# DC075B_DEVICE_PINOUT.net
KiCad netlist of a schematic drawn in Altium Designer
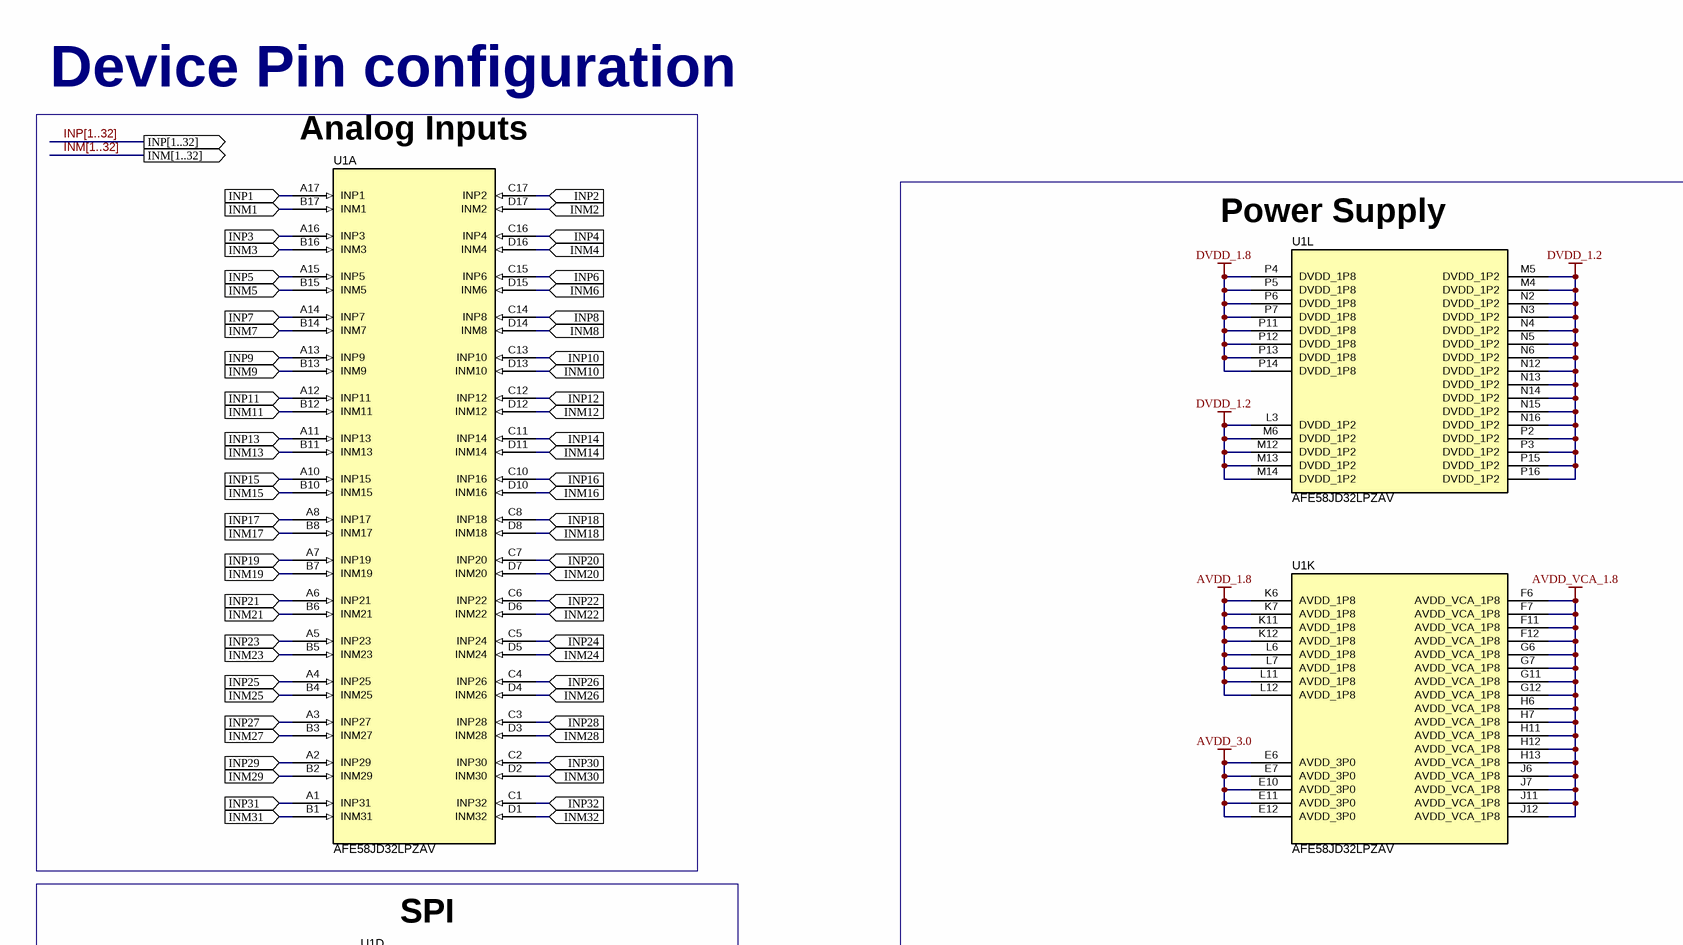
[diagram p0: DC075B_DEVICE_PINOUT.SchDoc, top left]
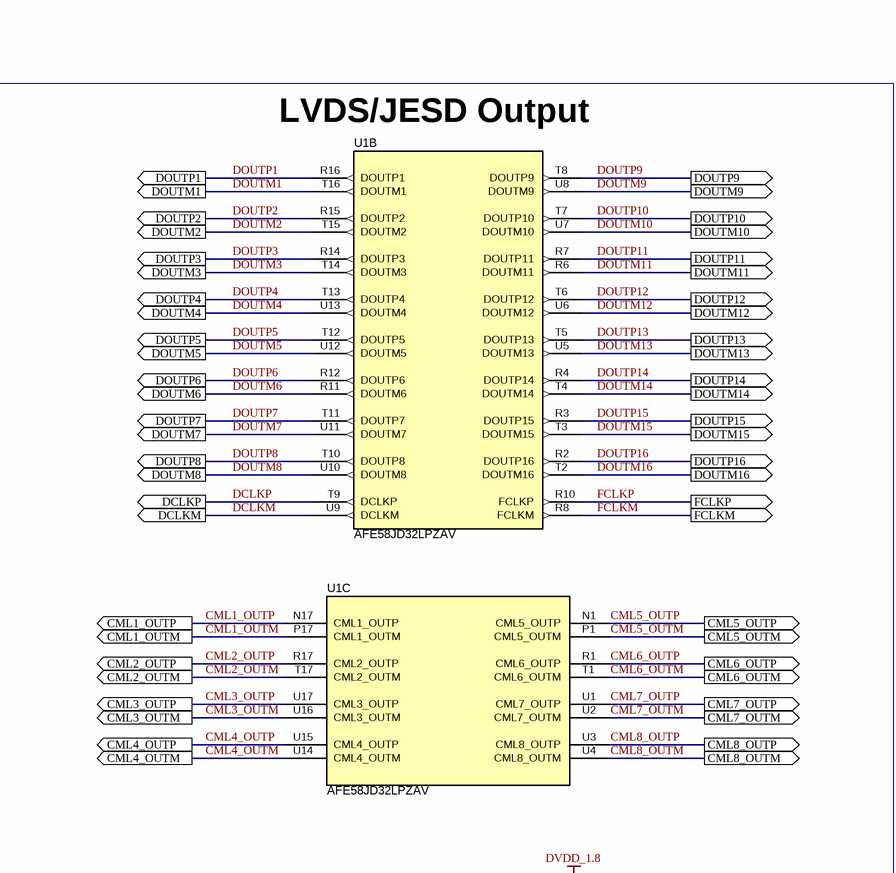
[diagram p1: DC075B_DEVICE_PINOUT.SchDoc, top right]
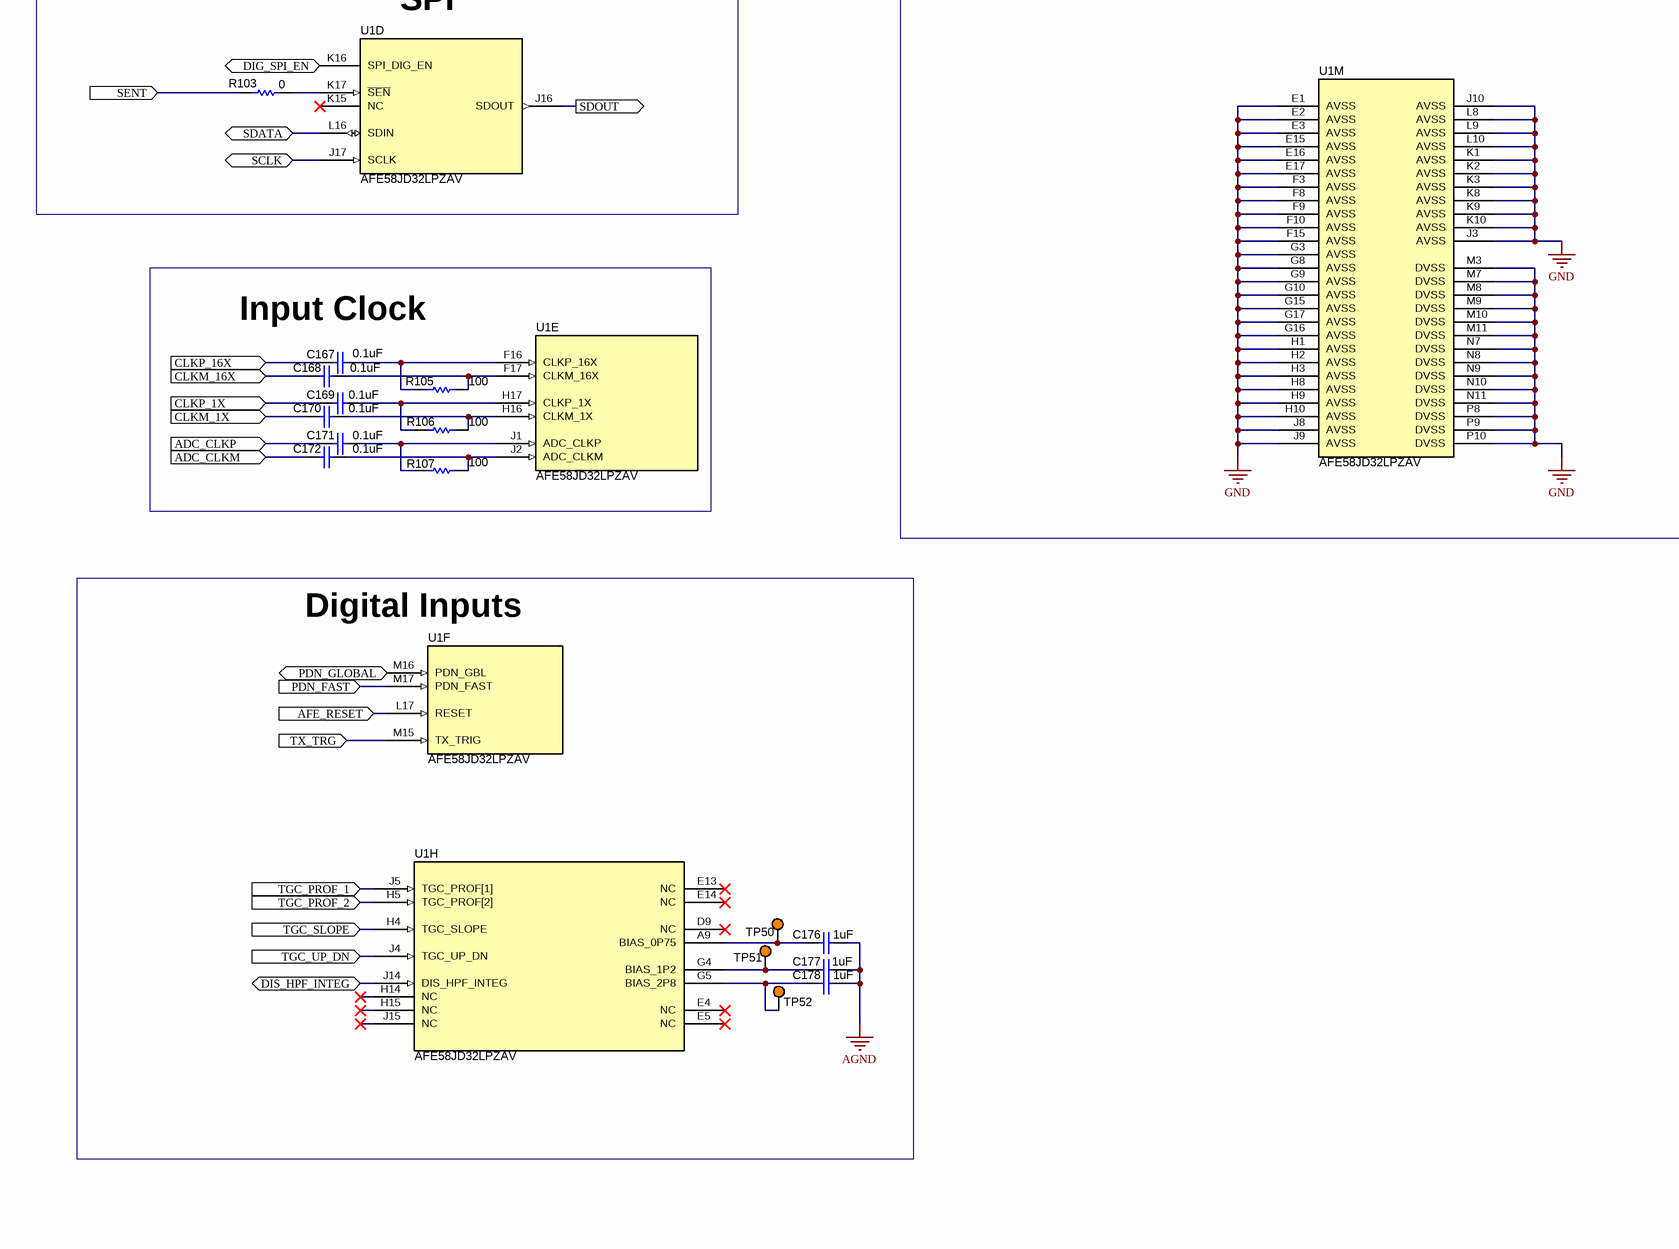
[diagram p2: DC075B_DEVICE_PINOUT.SchDoc, bottom left]
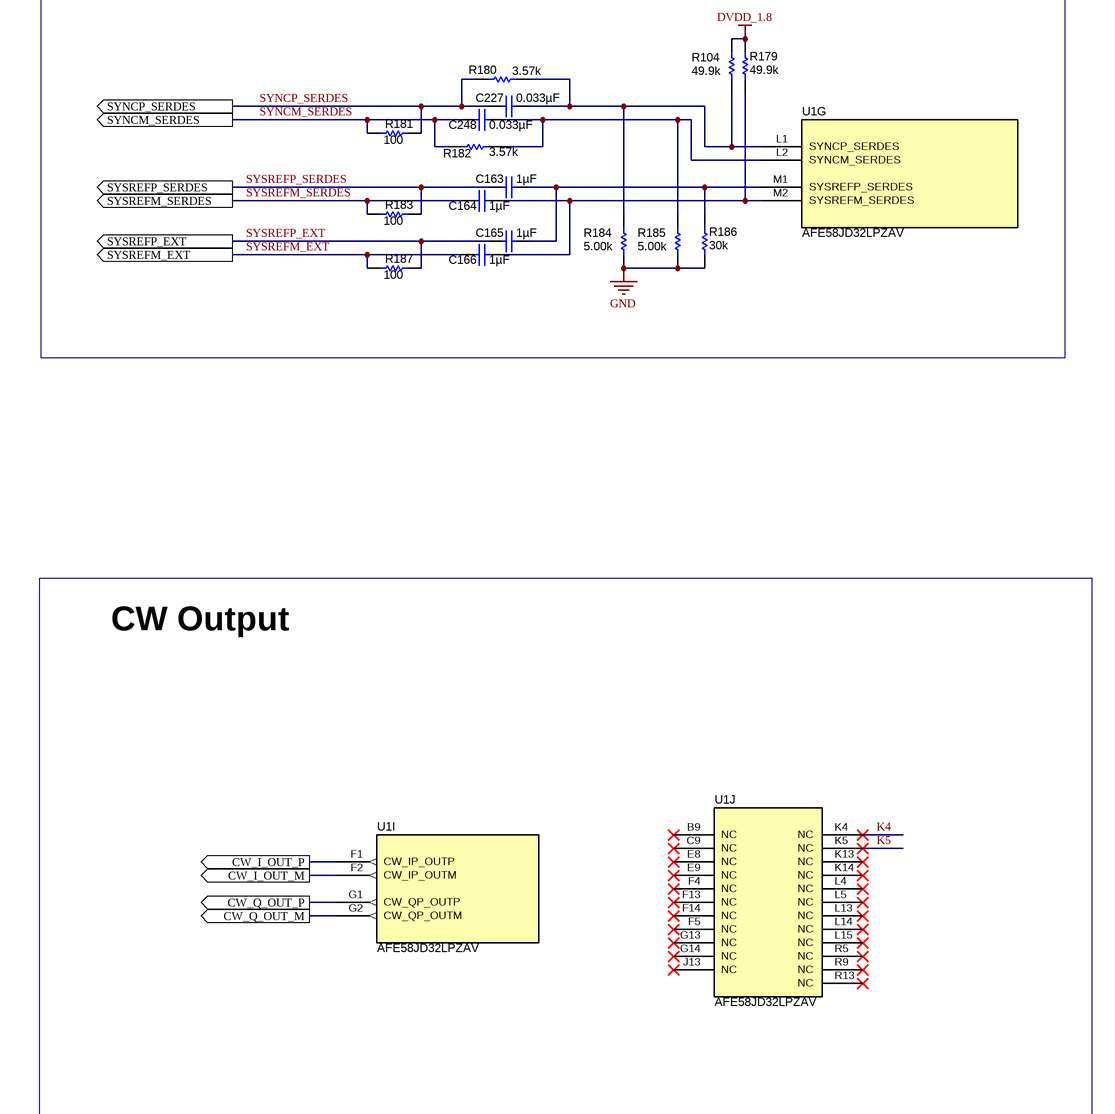
[diagram p3: DC075B_DEVICE_PINOUT.SchDoc, bottom right]

(export (version "E")
  (design (tool "Eeschema 10.0.6"))
  (components
    (comp (ref "C163")
      (value "CL05A105JQ5NNNC")
      (footprint "0402")
      (description "CAP, CERM, 1 µF, 6.3 V,+/- 5%, X5R, 0402")
      (fields (field (name "VALUEDISPLAYED") "1µF") (field (name "MANUFACTURER") "Samsung Electro-Mechanics"))
      (libsource (lib "Altium Vault - TI") (part "Capacitor"))
    )
    (comp (ref "C164")
      (value "CL05A105JQ5NNNC")
      (footprint "0402")
      (description "CAP, CERM, 1 µF, 6.3 V,+/- 5%, X5R, 0402")
      (fields (field (name "VALUEDISPLAYED") "1µF") (field (name "MANUFACTURER") "Samsung Electro-Mechanics"))
      (libsource (lib "Altium Vault - TI") (part "Capacitor"))
    )
    (comp (ref "C165")
      (value "CL05A105JQ5NNNC")
      (footprint "0402")
      (description "CAP, CERM, 1 µF, 6.3 V,+/- 5%, X5R, 0402")
      (fields (field (name "VALUEDISPLAYED") "1µF") (field (name "MANUFACTURER") "Samsung Electro-Mechanics"))
      (libsource (lib "Altium Vault - TI") (part "Capacitor"))
    )
    (comp (ref "C166")
      (value "CL05A105JQ5NNNC")
      (footprint "0402")
      (description "CAP, CERM, 1 µF, 6.3 V,+/- 5%, X5R, 0402")
      (fields (field (name "VALUEDISPLAYED") "1µF") (field (name "MANUFACTURER") "Samsung Electro-Mechanics"))
      (libsource (lib "Altium Vault - TI") (part "Capacitor"))
    )
    (comp (ref "C167")
      (value "0.1uF")
      (footprint "0402")
      (description "CAP, CERM, 0.1 uF, 16 V, +/- 10%, X7R, 0402")
      (fields
        (field (name "PARTNUMBER") "GRM155R71C104KA88D")
        (field (name "MANUFACTURER") "MuRata")
        (field (name "PUBLISHER") "Texas Instruments")
      )
      (libsource (lib "Altium Vault - TI") (part "Capacitor"))
    )
    (comp (ref "C168")
      (value "0.1uF")
      (footprint "0402")
      (description "CAP, CERM, 0.1 uF, 16 V, +/- 10%, X7R, 0402")
      (fields
        (field (name "PARTNUMBER") "GRM155R71C104KA88D")
        (field (name "MANUFACTURER") "MuRata")
        (field (name "PUBLISHER") "Texas Instruments")
      )
      (libsource (lib "Altium Vault - TI") (part "Capacitor"))
    )
    (comp (ref "C169")
      (value "0.1uF")
      (footprint "0402")
      (description "CAP, CERM, 0.1 uF, 16 V, +/- 10%, X7R, 0402")
      (fields
        (field (name "PARTNUMBER") "GRM155R71C104KA88D")
        (field (name "MANUFACTURER") "MuRata")
        (field (name "PUBLISHER") "Texas Instruments")
      )
      (libsource (lib "Altium Vault - TI") (part "Capacitor"))
    )
    (comp (ref "C170")
      (value "0.1uF")
      (footprint "0402")
      (description "CAP, CERM, 0.1 uF, 16 V, +/- 10%, X7R, 0402")
      (fields
        (field (name "PARTNUMBER") "GRM155R71C104KA88D")
        (field (name "MANUFACTURER") "MuRata")
        (field (name "PUBLISHER") "Texas Instruments")
      )
      (libsource (lib "Altium Vault - TI") (part "Capacitor"))
    )
    (comp (ref "C171")
      (value "0.1uF")
      (footprint "0402")
      (description "CAP, CERM, 0.1 uF, 16 V, +/- 10%, X7R, 0402")
      (fields
        (field (name "PARTNUMBER") "GRM155R71C104KA88D")
        (field (name "MANUFACTURER") "MuRata")
        (field (name "PUBLISHER") "Texas Instruments")
      )
      (libsource (lib "Altium Vault - TI") (part "Capacitor"))
    )
    (comp (ref "C172")
      (value "0.1uF")
      (footprint "0402")
      (description "CAP, CERM, 0.1 uF, 16 V, +/- 10%, X7R, 0402")
      (fields
        (field (name "PARTNUMBER") "GRM155R71C104KA88D")
        (field (name "MANUFACTURER") "MuRata")
        (field (name "PUBLISHER") "Texas Instruments")
      )
      (libsource (lib "Altium Vault - TI") (part "Capacitor"))
    )
    (comp (ref "C176")
      (value "1uF")
      (footprint "0402")
      (description "CAP, CERM, 1 uF, 6.3 V, +/- 20%, X5R, 0402")
      (fields
        (field (name "PARTNUMBER") "GRM152R60J105ME15D")
        (field (name "MANUFACTURER") "MuRata")
        (field (name "PUBLISHER") "Texas Instruments")
      )
      (libsource (lib "Altium Vault - TI") (part "Capacitor"))
    )
    (comp (ref "C177")
      (value "1uF")
      (footprint "0402")
      (description "CAP, CERM, 1 uF, 6.3 V, +/- 20%, X5R, 0402")
      (fields
        (field (name "PARTNUMBER") "GRM152R60J105ME15D")
        (field (name "MANUFACTURER") "MuRata")
        (field (name "PUBLISHER") "Texas Instruments")
      )
      (libsource (lib "Altium Vault - TI") (part "Capacitor"))
    )
    (comp (ref "C178")
      (value "1uF")
      (footprint "0402")
      (description "CAP, CERM, 1 uF, 6.3 V, +/- 20%, X5R, 0402")
      (fields
        (field (name "PARTNUMBER") "GRM152R60J105ME15D")
        (field (name "MANUFACTURER") "MuRata")
        (field (name "PUBLISHER") "Texas Instruments")
      )
      (libsource (lib "Altium Vault - TI") (part "Capacitor"))
    )
    (comp (ref "C227")
      (value "0402YD333KAT2A")
      (footprint "0402")
      (description "CAP, CERM, 0.033 µF, 16 V,+/- 10%, X5R, 0402")
      (fields (field (name "VALUEDISPLAYED") "0.033µF") (field (name "MANUFACTURER") "AVX"))
      (libsource (lib "Altium Vault - TI") (part "Capacitor"))
    )
    (comp (ref "C248")
      (value "0402YD333KAT2A")
      (footprint "0402")
      (description "CAP, CERM, 0.033 µF, 16 V,+/- 10%, X5R, 0402")
      (fields (field (name "VALUEDISPLAYED") "0.033µF") (field (name "MANUFACTURER") "AVX"))
      (libsource (lib "Altium Vault - TI") (part "Capacitor"))
    )
    (comp (ref "R103")
      (value "0")
      (footprint "0402")
      (description "RES, 0, 5%, 0.063 W, AEC-Q200 Grade 0, 0402")
      (fields (field (name "MANUFACTURER") "Vishay-Dale") (field (name "PARTNUMBER") "CRCW04020000Z0ED"))
      (libsource (lib "Altium Vault - TI") (part "Resistor"))
    )
    (comp (ref "R104")
      (value "Resistor")
      (footprint "0402")
      (description "RES, 49.9 k, 1%, 0.063 W, AEC-Q200 Grade 0, 0402")
      (fields
        (field (name "PARTNUMBER") "CRCW040249K9FKED")
        (field (name "VALUEDISPLAYED") "49.9k")
        (field (name "MANUFACTURER") "Vishay-Dale")
      )
      (libsource (lib "Altium Vault - TI") (part "Resistor"))
    )
    (comp (ref "R105")
      (value "Resistor")
      (footprint "0402")
      (description "RES, 100, 1%, 0.1 W, 0402")
      (fields
        (field (name "MANUFACTURER") "Panasonic")
        (field (name "PARTNUMBER") "ERJ-2RKF1000X")
        (field (name "VALUEDISPLAYED") "100")
        (field (name "PUBLISHER") "Texas Instruments")
      )
      (libsource (lib "Altium Vault - TI") (part "Resistor"))
    )
    (comp (ref "R106")
      (value "Resistor")
      (footprint "0402")
      (description "RES, 100, 1%, 0.1 W, 0402")
      (fields
        (field (name "MANUFACTURER") "Panasonic")
        (field (name "PARTNUMBER") "ERJ-2RKF1000X")
        (field (name "VALUEDISPLAYED") "100")
        (field (name "PUBLISHER") "Texas Instruments")
      )
      (libsource (lib "Altium Vault - TI") (part "Resistor"))
    )
    (comp (ref "R107")
      (value "Resistor")
      (footprint "0402")
      (description "RES, 100, 1%, 0.1 W, 0402")
      (fields
        (field (name "MANUFACTURER") "Panasonic")
        (field (name "PARTNUMBER") "ERJ-2RKF1000X")
        (field (name "VALUEDISPLAYED") "100")
        (field (name "PUBLISHER") "Texas Instruments")
      )
      (libsource (lib "Altium Vault - TI") (part "Resistor"))
    )
    (comp (ref "R179")
      (value "Resistor")
      (footprint "0402")
      (description "RES, 49.9 k, 1%, 0.063 W, AEC-Q200 Grade 0, 0402")
      (fields
        (field (name "PARTNUMBER") "CRCW040249K9FKED")
        (field (name "VALUEDISPLAYED") "49.9k")
        (field (name "MANUFACTURER") "Vishay-Dale")
      )
      (libsource (lib "Altium Vault - TI") (part "Resistor"))
    )
    (comp (ref "R180")
      (value "Resistor")
      (footprint "0402")
      (description "RES, 3.57 k, 1%, 0.063 W, AEC-Q200 Grade 0, 0402")
      (fields
        (field (name "PARTNUMBER") "CRCW04023K57FKED")
        (field (name "VALUEDISPLAYED") "3.57k")
        (field (name "MANUFACTURER") "Vishay-Dale")
      )
      (libsource (lib "Altium Vault - TI") (part "Resistor"))
    )
    (comp (ref "R181")
      (value "Resistor")
      (footprint "0402")
      (description "RES, 100, 1%, 0.1 W, 0402")
      (fields
        (field (name "MANUFACTURER") "Panasonic")
        (field (name "PARTNUMBER") "ERJ-2RKF1000X")
        (field (name "VALUEDISPLAYED") "100")
        (field (name "PUBLISHER") "Texas Instruments")
      )
      (libsource (lib "Altium Vault - TI") (part "Resistor"))
    )
    (comp (ref "R182")
      (value "Resistor")
      (footprint "0402")
      (description "RES, 3.57 k, 1%, 0.063 W, AEC-Q200 Grade 0, 0402")
      (fields
        (field (name "PARTNUMBER") "CRCW04023K57FKED")
        (field (name "VALUEDISPLAYED") "3.57k")
        (field (name "MANUFACTURER") "Vishay-Dale")
      )
      (libsource (lib "Altium Vault - TI") (part "Resistor"))
    )
    (comp (ref "R183")
      (value "Resistor")
      (footprint "0402")
      (description "RES, 100, 1%, 0.1 W, 0402")
      (fields
        (field (name "MANUFACTURER") "Panasonic")
        (field (name "PARTNUMBER") "ERJ-2RKF1000X")
        (field (name "VALUEDISPLAYED") "100")
        (field (name "PUBLISHER") "Texas Instruments")
      )
      (libsource (lib "Altium Vault - TI") (part "Resistor"))
    )
    (comp (ref "R184")
      (value "Resistor")
      (footprint "0402")
      (description "RES, 5.00 k, 0.1%, 0.05 W, 0402")
      (fields
        (field (name "PARTNUMBER") "PNM0402E5001BST1")
        (field (name "VALUEDISPLAYED") "5.00k")
        (field (name "MANUFACTURER") "Vishay-Dale")
        (field (name "PUBLISHER") "Texas Instruments")
      )
      (libsource (lib "Altium Vault - TI") (part "Resistor"))
    )
    (comp (ref "R185")
      (value "Resistor")
      (footprint "0402")
      (description "RES, 5.00 k, 0.1%, 0.05 W, 0402")
      (fields
        (field (name "PARTNUMBER") "PNM0402E5001BST1")
        (field (name "VALUEDISPLAYED") "5.00k")
        (field (name "MANUFACTURER") "Vishay-Dale")
        (field (name "PUBLISHER") "Texas Instruments")
      )
      (libsource (lib "Altium Vault - TI") (part "Resistor"))
    )
    (comp (ref "R186")
      (value "Resistor")
      (footprint "0402")
      (description "RES, 30 k, 5%, 0.063 W, AEC-Q200 Grade 0, 0402")
      (fields
        (field (name "PARTNUMBER") "CRCW040230K0JNED")
        (field (name "VALUEDISPLAYED") "30k")
        (field (name "MANUFACTURER") "Vishay-Dale")
      )
      (libsource (lib "Altium Vault - TI") (part "Resistor"))
    )
    (comp (ref "R187")
      (value "Resistor")
      (footprint "0402")
      (description "RES, 100, 1%, 0.1 W, 0402")
      (fields
        (field (name "MANUFACTURER") "Panasonic")
        (field (name "PARTNUMBER") "ERJ-2RKF1000X")
        (field (name "VALUEDISPLAYED") "100")
        (field (name "PUBLISHER") "Texas Instruments")
      )
      (libsource (lib "Altium Vault - TI") (part "Resistor"))
    )
    (comp (ref "TP50")
      (value "5003")
      (footprint "Keystone5003")
      (description "Test Point, Miniature, Orange, TH")
      (fields (field (name "MANUFACTURER") "Keystone") (field (name "PUBLISHER") "Texas Instruments"))
      (libsource (lib "Altium Vault - TI") (part "5003"))
    )
    (comp (ref "TP51")
      (value "5003")
      (footprint "Keystone5003")
      (description "Test Point, Miniature, Orange, TH")
      (fields (field (name "MANUFACTURER") "Keystone") (field (name "PUBLISHER") "Texas Instruments"))
      (libsource (lib "Altium Vault - TI") (part "5003"))
    )
    (comp (ref "TP52")
      (value "5003")
      (footprint "Keystone5003")
      (description "Test Point, Miniature, Orange, TH")
      (fields (field (name "MANUFACTURER") "Keystone") (field (name "PUBLISHER") "Texas Instruments"))
      (libsource (lib "Altium Vault - TI") (part "5003"))
    )
    (comp (ref "U1")
      (value "AFE58JD32LPZAV")
      (footprint "ZAV0289A")
      (fields (field (name "PARTNUMBER") "AFE58JD32LPZAV") (field (name "MANUFACTURER") "Texas Instruments"))
      (libsource (lib "Altium Vault - TI") (part "AFE58JD32LP"))
    )
  )
  (nets
    (net (code "1") (name "/ADC_CLKM") (class "Default")
      (node (ref "C172") (pin "2") (pinfunction "2_2") (pintype "passive"))
    )
    (net (code "2") (name "/ADC_CLKP") (class "Default")
      (node (ref "C171") (pin "2") (pinfunction "2_2") (pintype "passive"))
    )
    (net (code "3") (name "/AFE_RESET") (class "Default")
      (node (ref "U1") (pin "L17") (pinfunction "RESET_L17") (pintype "input"))
    )
    (net (code "4") (name "/CLKM_1X") (class "Default")
      (node (ref "C170") (pin "2") (pinfunction "2_2") (pintype "passive"))
    )
    (net (code "5") (name "/CLKM_16X") (class "Default")
      (node (ref "C168") (pin "2") (pinfunction "2_2") (pintype "passive"))
    )
    (net (code "6") (name "/CLKP_1X") (class "Default")
      (node (ref "C169") (pin "2") (pinfunction "2_2") (pintype "passive"))
    )
    (net (code "7") (name "/CLKP_16X") (class "Default")
      (node (ref "C167") (pin "2") (pinfunction "2_2") (pintype "passive"))
    )
    (net (code "8") (name "/CML1_OUTM") (class "Default")
      (node (ref "U1") (pin "P17") (pinfunction "CML1_OUTM_P17") (pintype "open_collector"))
    )
    (net (code "9") (name "/CML1_OUTP") (class "Default")
      (node (ref "U1") (pin "N17") (pinfunction "CML1_OUTP_N17") (pintype "open_collector"))
    )
    (net (code "10") (name "/CML2_OUTM") (class "Default")
      (node (ref "U1") (pin "T17") (pinfunction "CML2_OUTM_T17") (pintype "open_collector"))
    )
    (net (code "11") (name "/CML2_OUTP") (class "Default")
      (node (ref "U1") (pin "R17") (pinfunction "CML2_OUTP_R17") (pintype "open_collector"))
    )
    (net (code "12") (name "/CML3_OUTM") (class "Default")
      (node (ref "U1") (pin "U16") (pinfunction "CML3_OUTM_U16") (pintype "open_collector"))
    )
    (net (code "13") (name "/CML3_OUTP") (class "Default")
      (node (ref "U1") (pin "U17") (pinfunction "CML3_OUTP_U17") (pintype "open_collector"))
    )
    (net (code "14") (name "/CML4_OUTM") (class "Default")
      (node (ref "U1") (pin "U14") (pinfunction "CML4_OUTM_U14") (pintype "open_collector"))
    )
    (net (code "15") (name "/CML4_OUTP") (class "Default")
      (node (ref "U1") (pin "U15") (pinfunction "CML4_OUTP_U15") (pintype "open_collector"))
    )
    (net (code "16") (name "/CML5_OUTM") (class "Default")
      (node (ref "U1") (pin "P1") (pinfunction "CML5_OUTM_P1") (pintype "open_collector"))
    )
    (net (code "17") (name "/CML5_OUTP") (class "Default")
      (node (ref "U1") (pin "N1") (pinfunction "CML5_OUTP_N1") (pintype "open_collector"))
    )
    (net (code "18") (name "/CML6_OUTM") (class "Default")
      (node (ref "U1") (pin "T1") (pinfunction "CML6_OUTM_T1") (pintype "open_collector"))
    )
    (net (code "19") (name "/CML6_OUTP") (class "Default")
      (node (ref "U1") (pin "R1") (pinfunction "CML6_OUTP_R1") (pintype "open_collector"))
    )
    (net (code "20") (name "/CML7_OUTM") (class "Default")
      (node (ref "U1") (pin "U2") (pinfunction "CML7_OUTM_U2") (pintype "open_collector"))
    )
    (net (code "21") (name "/CML7_OUTP") (class "Default")
      (node (ref "U1") (pin "U1") (pinfunction "CML7_OUTP_U1") (pintype "open_collector"))
    )
    (net (code "22") (name "/CML8_OUTM") (class "Default")
      (node (ref "U1") (pin "U4") (pinfunction "CML8_OUTM_U4") (pintype "open_collector"))
    )
    (net (code "23") (name "/CML8_OUTP") (class "Default")
      (node (ref "U1") (pin "U3") (pinfunction "CML8_OUTP_U3") (pintype "open_collector"))
    )
    (net (code "24") (name "/CW_I_OUT_M") (class "Default")
      (node (ref "U1") (pin "F2") (pinfunction "CW_IP_OUTM_F2") (pintype "output"))
    )
    (net (code "25") (name "/CW_I_OUT_P") (class "Default")
      (node (ref "U1") (pin "F1") (pinfunction "CW_IP_OUTP_F1") (pintype "output"))
    )
    (net (code "26") (name "/CW_Q_OUT_M") (class "Default")
      (node (ref "U1") (pin "G2") (pinfunction "CW_QP_OUTM_G2") (pintype "output"))
    )
    (net (code "27") (name "/CW_Q_OUT_P") (class "Default")
      (node (ref "U1") (pin "G1") (pinfunction "CW_QP_OUTP_G1") (pintype "output"))
    )
    (net (code "28") (name "/DCLKM") (class "Default")
      (node (ref "U1") (pin "U9") (pinfunction "DCLKM_U9") (pintype "output"))
    )
    (net (code "29") (name "/DCLKP") (class "Default")
      (node (ref "U1") (pin "T9") (pinfunction "DCLKP_T9") (pintype "output"))
    )
    (net (code "30") (name "/DIG_SPI_EN") (class "Default")
      (node (ref "U1") (pin "K16") (pinfunction "SPI_DIG_EN_K16") (pintype "passive"))
    )
    (net (code "31") (name "/DIS_HPF_INTEG") (class "Default")
      (node (ref "U1") (pin "J14") (pinfunction "DIS_HPF_INTEG_J14") (pintype "input"))
    )
    (net (code "32") (name "/DOUTM1") (class "Default")
      (node (ref "U1") (pin "T16") (pinfunction "DOUTM1_T16") (pintype "output"))
    )
    (net (code "33") (name "/DOUTM2") (class "Default")
      (node (ref "U1") (pin "T15") (pinfunction "DOUTM2_T15") (pintype "output"))
    )
    (net (code "34") (name "/DOUTM3") (class "Default")
      (node (ref "U1") (pin "T14") (pinfunction "DOUTM3_T14") (pintype "output"))
    )
    (net (code "35") (name "/DOUTM4") (class "Default")
      (node (ref "U1") (pin "U13") (pinfunction "DOUTM4_U13") (pintype "output"))
    )
    (net (code "36") (name "/DOUTM5") (class "Default")
      (node (ref "U1") (pin "U12") (pinfunction "DOUTM5_U12") (pintype "output"))
    )
    (net (code "37") (name "/DOUTM6") (class "Default")
      (node (ref "U1") (pin "R11") (pinfunction "DOUTM6_R11") (pintype "output"))
    )
    (net (code "38") (name "/DOUTM7") (class "Default")
      (node (ref "U1") (pin "U11") (pinfunction "DOUTM7_U11") (pintype "output"))
    )
    (net (code "39") (name "/DOUTM8") (class "Default")
      (node (ref "U1") (pin "U10") (pinfunction "DOUTM8_U10") (pintype "output"))
    )
    (net (code "40") (name "/DOUTM9") (class "Default")
      (node (ref "U1") (pin "U8") (pinfunction "DOUTM9_U8") (pintype "output"))
    )
    (net (code "41") (name "/DOUTM10") (class "Default")
      (node (ref "U1") (pin "U7") (pinfunction "DOUTM10_U7") (pintype "output"))
    )
    (net (code "42") (name "/DOUTM11") (class "Default")
      (node (ref "U1") (pin "R6") (pinfunction "DOUTM11_R6") (pintype "output"))
    )
    (net (code "43") (name "/DOUTM12") (class "Default")
      (node (ref "U1") (pin "U6") (pinfunction "DOUTM12_U6") (pintype "output"))
    )
    (net (code "44") (name "/DOUTM13") (class "Default")
      (node (ref "U1") (pin "U5") (pinfunction "DOUTM13_U5") (pintype "output"))
    )
    (net (code "45") (name "/DOUTM14") (class "Default")
      (node (ref "U1") (pin "T4") (pinfunction "DOUTM14_T4") (pintype "output"))
    )
    (net (code "46") (name "/DOUTM15") (class "Default")
      (node (ref "U1") (pin "T3") (pinfunction "DOUTM15_T3") (pintype "output"))
    )
    (net (code "47") (name "/DOUTM16") (class "Default")
      (node (ref "U1") (pin "T2") (pinfunction "DOUTM16_T2") (pintype "output"))
    )
    (net (code "48") (name "/DOUTP1") (class "Default")
      (node (ref "U1") (pin "R16") (pinfunction "DOUTP1_R16") (pintype "output"))
    )
    (net (code "49") (name "/DOUTP2") (class "Default")
      (node (ref "U1") (pin "R15") (pinfunction "DOUTP2_R15") (pintype "output"))
    )
    (net (code "50") (name "/DOUTP3") (class "Default")
      (node (ref "U1") (pin "R14") (pinfunction "DOUTP3_R14") (pintype "output"))
    )
    (net (code "51") (name "/DOUTP4") (class "Default")
      (node (ref "U1") (pin "T13") (pinfunction "DOUTP4_T13") (pintype "output"))
    )
    (net (code "52") (name "/DOUTP5") (class "Default")
      (node (ref "U1") (pin "T12") (pinfunction "DOUTP5_T12") (pintype "output"))
    )
    (net (code "53") (name "/DOUTP6") (class "Default")
      (node (ref "U1") (pin "R12") (pinfunction "DOUTP6_R12") (pintype "output"))
    )
    (net (code "54") (name "/DOUTP7") (class "Default")
      (node (ref "U1") (pin "T11") (pinfunction "DOUTP7_T11") (pintype "output"))
    )
    (net (code "55") (name "/DOUTP8") (class "Default")
      (node (ref "U1") (pin "T10") (pinfunction "DOUTP8_T10") (pintype "output"))
    )
    (net (code "56") (name "/DOUTP9") (class "Default")
      (node (ref "U1") (pin "T8") (pinfunction "DOUTP9_T8") (pintype "output"))
    )
    (net (code "57") (name "/DOUTP10") (class "Default")
      (node (ref "U1") (pin "T7") (pinfunction "DOUTP10_T7") (pintype "output"))
    )
    (net (code "58") (name "/DOUTP11") (class "Default")
      (node (ref "U1") (pin "R7") (pinfunction "DOUTP11_R7") (pintype "output"))
    )
    (net (code "59") (name "/DOUTP12") (class "Default")
      (node (ref "U1") (pin "T6") (pinfunction "DOUTP12_T6") (pintype "output"))
    )
    (net (code "60") (name "/DOUTP13") (class "Default")
      (node (ref "U1") (pin "T5") (pinfunction "DOUTP13_T5") (pintype "output"))
    )
    (net (code "61") (name "/DOUTP14") (class "Default")
      (node (ref "U1") (pin "R4") (pinfunction "DOUTP14_R4") (pintype "output"))
    )
    (net (code "62") (name "/DOUTP15") (class "Default")
      (node (ref "U1") (pin "R3") (pinfunction "DOUTP15_R3") (pintype "output"))
    )
    (net (code "63") (name "/DOUTP16") (class "Default")
      (node (ref "U1") (pin "R2") (pinfunction "DOUTP16_R2") (pintype "output"))
    )
    (net (code "64") (name "/FCLKM") (class "Default")
      (node (ref "U1") (pin "R8") (pinfunction "FCLKM_R8") (pintype "output"))
    )
    (net (code "65") (name "/FCLKP") (class "Default")
      (node (ref "U1") (pin "R10") (pinfunction "FCLKP_R10") (pintype "output"))
    )
    (net (code "66") (name "/INM1") (class "Default")
      (node (ref "U1") (pin "B17") (pinfunction "INM1_B17") (pintype "input"))
    )
    (net (code "67") (name "/INM2") (class "Default")
      (node (ref "U1") (pin "D17") (pinfunction "INM2_D17") (pintype "input"))
    )
    (net (code "68") (name "/INM3") (class "Default")
      (node (ref "U1") (pin "B16") (pinfunction "INM3_B16") (pintype "input"))
    )
    (net (code "69") (name "/INM4") (class "Default")
      (node (ref "U1") (pin "D16") (pinfunction "INM4_D16") (pintype "input"))
    )
    (net (code "70") (name "/INM5") (class "Default")
      (node (ref "U1") (pin "B15") (pinfunction "INM5_B15") (pintype "input"))
    )
    (net (code "71") (name "/INM6") (class "Default")
      (node (ref "U1") (pin "D15") (pinfunction "INM6_D15") (pintype "input"))
    )
    (net (code "72") (name "/INM7") (class "Default")
      (node (ref "U1") (pin "B14") (pinfunction "INM7_B14") (pintype "input"))
    )
    (net (code "73") (name "/INM8") (class "Default")
      (node (ref "U1") (pin "D14") (pinfunction "INM8_D14") (pintype "input"))
    )
    (net (code "74") (name "/INM9") (class "Default")
      (node (ref "U1") (pin "B13") (pinfunction "INM9_B13") (pintype "input"))
    )
    (net (code "75") (name "/INM10") (class "Default")
      (node (ref "U1") (pin "D13") (pinfunction "INM10_D13") (pintype "input"))
    )
    (net (code "76") (name "/INM11") (class "Default")
      (node (ref "U1") (pin "B12") (pinfunction "INM11_B12") (pintype "input"))
    )
    (net (code "77") (name "/INM12") (class "Default")
      (node (ref "U1") (pin "D12") (pinfunction "INM12_D12") (pintype "input"))
    )
    (net (code "78") (name "/INM13") (class "Default")
      (node (ref "U1") (pin "B11") (pinfunction "INM13_B11") (pintype "input"))
    )
    (net (code "79") (name "/INM14") (class "Default")
      (node (ref "U1") (pin "D11") (pinfunction "INM14_D11") (pintype "input"))
    )
    (net (code "80") (name "/INM15") (class "Default")
      (node (ref "U1") (pin "B10") (pinfunction "INM15_B10") (pintype "input"))
    )
    (net (code "81") (name "/INM16") (class "Default")
      (node (ref "U1") (pin "D10") (pinfunction "INM16_D10") (pintype "input"))
    )
    (net (code "82") (name "/INM17") (class "Default")
      (node (ref "U1") (pin "B8") (pinfunction "INM17_B8") (pintype "input"))
    )
    (net (code "83") (name "/INM18") (class "Default")
      (node (ref "U1") (pin "D8") (pinfunction "INM18_D8") (pintype "input"))
    )
    (net (code "84") (name "/INM19") (class "Default")
      (node (ref "U1") (pin "B7") (pinfunction "INM19_B7") (pintype "input"))
    )
    (net (code "85") (name "/INM20") (class "Default")
      (node (ref "U1") (pin "D7") (pinfunction "INM20_D7") (pintype "input"))
    )
    (net (code "86") (name "/INM21") (class "Default")
      (node (ref "U1") (pin "B6") (pinfunction "INM21_B6") (pintype "input"))
    )
    (net (code "87") (name "/INM22") (class "Default")
      (node (ref "U1") (pin "D6") (pinfunction "INM22_D6") (pintype "input"))
    )
    (net (code "88") (name "/INM23") (class "Default")
      (node (ref "U1") (pin "B5") (pinfunction "INM23_B5") (pintype "input"))
    )
    (net (code "89") (name "/INM24") (class "Default")
      (node (ref "U1") (pin "D5") (pinfunction "INM24_D5") (pintype "input"))
    )
    (net (code "90") (name "/INM25") (class "Default")
      (node (ref "U1") (pin "B4") (pinfunction "INM25_B4") (pintype "input"))
    )
    (net (code "91") (name "/INM26") (class "Default")
      (node (ref "U1") (pin "D4") (pinfunction "INM26_D4") (pintype "input"))
    )
    (net (code "92") (name "/INM27") (class "Default")
      (node (ref "U1") (pin "B3") (pinfunction "INM27_B3") (pintype "input"))
    )
    (net (code "93") (name "/INM28") (class "Default")
      (node (ref "U1") (pin "D3") (pinfunction "INM28_D3") (pintype "input"))
    )
    (net (code "94") (name "/INM29") (class "Default")
      (node (ref "U1") (pin "B2") (pinfunction "INM29_B2") (pintype "input"))
    )
    (net (code "95") (name "/INM30") (class "Default")
      (node (ref "U1") (pin "D2") (pinfunction "INM30_D2") (pintype "input"))
    )
    (net (code "96") (name "/INM31") (class "Default")
      (node (ref "U1") (pin "B1") (pinfunction "INM31_B1") (pintype "input"))
    )
    (net (code "97") (name "/INM32") (class "Default")
      (node (ref "U1") (pin "D1") (pinfunction "INM32_D1") (pintype "input"))
    )
    (net (code "99") (name "/INP1") (class "Default")
      (node (ref "U1") (pin "A17") (pinfunction "INP1_A17") (pintype "input"))
    )
    (net (code "100") (name "/INP2") (class "Default")
      (node (ref "U1") (pin "C17") (pinfunction "INP2_C17") (pintype "input"))
    )
    (net (code "101") (name "/INP3") (class "Default")
      (node (ref "U1") (pin "A16") (pinfunction "INP3_A16") (pintype "input"))
    )
    (net (code "102") (name "/INP4") (class "Default")
      (node (ref "U1") (pin "C16") (pinfunction "INP4_C16") (pintype "input"))
    )
    (net (code "103") (name "/INP5") (class "Default")
      (node (ref "U1") (pin "A15") (pinfunction "INP5_A15") (pintype "input"))
    )
    (net (code "104") (name "/INP6") (class "Default")
      (node (ref "U1") (pin "C15") (pinfunction "INP6_C15") (pintype "input"))
    )
    (net (code "105") (name "/INP7") (class "Default")
      (node (ref "U1") (pin "A14") (pinfunction "INP7_A14") (pintype "input"))
    )
    (net (code "106") (name "/INP8") (class "Default")
      (node (ref "U1") (pin "C14") (pinfunction "INP8_C14") (pintype "input"))
    )
    (net (code "107") (name "/INP9") (class "Default")
      (node (ref "U1") (pin "A13") (pinfunction "INP9_A13") (pintype "input"))
    )
    (net (code "108") (name "/INP10") (class "Default")
      (node (ref "U1") (pin "C13") (pinfunction "INP10_C13") (pintype "input"))
    )
    (net (code "109") (name "/INP11") (class "Default")
      (node (ref "U1") (pin "A12") (pinfunction "INP11_A12") (pintype "input"))
    )
    (net (code "110") (name "/INP12") (class "Default")
      (node (ref "U1") (pin "C12") (pinfunction "INP12_C12") (pintype "input"))
    )
    (net (code "111") (name "/INP13") (class "Default")
      (node (ref "U1") (pin "A11") (pinfunction "INP13_A11") (pintype "input"))
    )
    (net (code "112") (name "/INP14") (class "Default")
      (node (ref "U1") (pin "C11") (pinfunction "INP14_C11") (pintype "input"))
    )
    (net (code "113") (name "/INP15") (class "Default")
      (node (ref "U1") (pin "A10") (pinfunction "INP15_A10") (pintype "input"))
    )
    (net (code "114") (name "/INP16") (class "Default")
      (node (ref "U1") (pin "C10") (pinfunction "INP16_C10") (pintype "input"))
    )
    (net (code "115") (name "/INP17") (class "Default")
      (node (ref "U1") (pin "A8") (pinfunction "INP17_A8") (pintype "input"))
    )
    (net (code "116") (name "/INP18") (class "Default")
      (node (ref "U1") (pin "C8") (pinfunction "INP18_C8") (pintype "input"))
    )
    (net (code "117") (name "/INP19") (class "Default")
      (node (ref "U1") (pin "A7") (pinfunction "INP19_A7") (pintype "input"))
    )
    (net (code "118") (name "/INP20") (class "Default")
      (node (ref "U1") (pin "C7") (pinfunction "INP20_C7") (pintype "input"))
    )
    (net (code "119") (name "/INP21") (class "Default")
      (node (ref "U1") (pin "A6") (pinfunction "INP21_A6") (pintype "input"))
    )
    (net (code "120") (name "/INP22") (class "Default")
      (node (ref "U1") (pin "C6") (pinfunction "INP22_C6") (pintype "input"))
    )
    (net (code "121") (name "/INP23") (class "Default")
      (node (ref "U1") (pin "A5") (pinfunction "INP23_A5") (pintype "input"))
    )
    (net (code "122") (name "/INP24") (class "Default")
      (node (ref "U1") (pin "C5") (pinfunction "INP24_C5") (pintype "input"))
    )
    (net (code "123") (name "/INP25") (class "Default")
      (node (ref "U1") (pin "A4") (pinfunction "INP25_A4") (pintype "input"))
    )
    (net (code "124") (name "/INP26") (class "Default")
      (node (ref "U1") (pin "C4") (pinfunction "INP26_C4") (pintype "input"))
    )
    (net (code "125") (name "/INP27") (class "Default")
      (node (ref "U1") (pin "A3") (pinfunction "INP27_A3") (pintype "input"))
    )
    (net (code "126") (name "/INP28") (class "Default")
      (node (ref "U1") (pin "C3") (pinfunction "INP28_C3") (pintype "input"))
    )
    (net (code "127") (name "/INP29") (class "Default")
      (node (ref "U1") (pin "A2") (pinfunction "INP29_A2") (pintype "input"))
    )
    (net (code "128") (name "/INP30") (class "Default")
      (node (ref "U1") (pin "C2") (pinfunction "INP30_C2") (pintype "input"))
    )
    (net (code "129") (name "/INP31") (class "Default")
      (node (ref "U1") (pin "A1") (pinfunction "INP31_A1") (pintype "input"))
    )
    (net (code "130") (name "/INP32") (class "Default")
      (node (ref "U1") (pin "C1") (pinfunction "INP32_C1") (pintype "input"))
    )
    (net (code "132") (name "/K4") (class "Default")
      (node (ref "U1") (pin "K4") (pinfunction "NC_K4") (pintype "passive+no_connect"))
    )
    (net (code "133") (name "/K5") (class "Default")
      (node (ref "U1") (pin "K5") (pinfunction "NC_K5") (pintype "passive+no_connect"))
    )
    (net (code "134") (name "/PDN_FAST") (class "Default")
      (node (ref "U1") (pin "M17") (pinfunction "PDN_FAST_M17") (pintype "input"))
    )
    (net (code "135") (name "/PDN_GLOBAL") (class "Default")
      (node (ref "U1") (pin "M16") (pinfunction "PDN_GBL_M16") (pintype "input"))
    )
    (net (code "136") (name "/SCLK") (class "Default")
      (node (ref "U1") (pin "J17") (pinfunction "SCLK_J17") (pintype "input"))
    )
    (net (code "137") (name "/SDATA") (class "Default")
      (node (ref "U1") (pin "L16") (pinfunction "SDIN_L16") (pintype "bidirectional"))
    )
    (net (code "138") (name "/SDOUT") (class "Default")
      (node (ref "U1") (pin "J16") (pinfunction "SDOUT_J16") (pintype "output"))
    )
    (net (code "139") (name "/SENT") (class "Default")
      (node (ref "R103") (pin "1") (pinfunction "1_1") (pintype "passive"))
    )
    (net (code "140") (name "/SYNCM_SERDES") (class "Default")
      (node (ref "C248") (pin "2") (pinfunction "2_2") (pintype "passive"))
      (node (ref "R181") (pin "1") (pinfunction "1_1") (pintype "passive"))
      (node (ref "R182") (pin "1") (pinfunction "1_1") (pintype "passive"))
    )
    (net (code "141") (name "/SYNCP_SERDES") (class "Default")
      (node (ref "C227") (pin "2") (pinfunction "2_2") (pintype "passive"))
      (node (ref "R180") (pin "1") (pinfunction "1_1") (pintype "passive"))
      (node (ref "R181") (pin "2") (pinfunction "2_2") (pintype "passive"))
    )
    (net (code "142") (name "/SYSREFM_EXT") (class "Default")
      (node (ref "C166") (pin "2") (pinfunction "2_2") (pintype "passive"))
      (node (ref "R187") (pin "1") (pinfunction "1_1") (pintype "passive"))
    )
    (net (code "143") (name "/SYSREFM_SERDES") (class "Default")
      (node (ref "C164") (pin "2") (pinfunction "2_2") (pintype "passive"))
      (node (ref "R183") (pin "1") (pinfunction "1_1") (pintype "passive"))
    )
    (net (code "144") (name "/SYSREFP_EXT") (class "Default")
      (node (ref "C165") (pin "2") (pinfunction "2_2") (pintype "passive"))
      (node (ref "R187") (pin "2") (pinfunction "2_2") (pintype "passive"))
    )
    (net (code "145") (name "/SYSREFP_SERDES") (class "Default")
      (node (ref "C163") (pin "2") (pinfunction "2_2") (pintype "passive"))
      (node (ref "R183") (pin "2") (pinfunction "2_2") (pintype "passive"))
    )
    (net (code "146") (name "/TGC_PROF_1") (class "Default")
      (node (ref "U1") (pin "J5") (pinfunction "TGC_PROF[1]_J5") (pintype "input"))
    )
    (net (code "147") (name "/TGC_PROF_2") (class "Default")
      (node (ref "U1") (pin "H5") (pinfunction "TGC_PROF[2]_H5") (pintype "input"))
    )
    (net (code "148") (name "/TGC_SLOPE") (class "Default")
      (node (ref "U1") (pin "H4") (pinfunction "TGC_SLOPE_H4") (pintype "input"))
    )
    (net (code "149") (name "/TGC_UP_DN") (class "Default")
      (node (ref "U1") (pin "J4") (pinfunction "TGC_UP_DN_J4") (pintype "input"))
    )
    (net (code "150") (name "/TX_TRG") (class "Default")
      (node (ref "U1") (pin "M15") (pinfunction "TX_TRIG_M15") (pintype "input"))
    )
    (net (code "151") (name "AGND") (class "Default")
      (node (ref "C176") (pin "2") (pinfunction "2_2") (pintype "passive"))
      (node (ref "C177") (pin "2") (pinfunction "2_2") (pintype "passive"))
      (node (ref "C178") (pin "2") (pinfunction "2_2") (pintype "passive"))
    )
    (net (code "152") (name "AVDD_1.8") (class "Default")
      (node (ref "U1") (pin "K11") (pinfunction "AVDD_1P8_K11") (pintype "power_in"))
      (node (ref "U1") (pin "K12") (pinfunction "AVDD_1P8_K12") (pintype "power_in"))
      (node (ref "U1") (pin "K6") (pinfunction "AVDD_1P8_K6") (pintype "power_in"))
      (node (ref "U1") (pin "K7") (pinfunction "AVDD_1P8_K7") (pintype "power_in"))
      (node (ref "U1") (pin "L11") (pinfunction "AVDD_1P8_L11") (pintype "power_in"))
      (node (ref "U1") (pin "L12") (pinfunction "AVDD_1P8_L12") (pintype "power_in"))
      (node (ref "U1") (pin "L6") (pinfunction "AVDD_1P8_L6") (pintype "power_in"))
      (node (ref "U1") (pin "L7") (pinfunction "AVDD_1P8_L7") (pintype "power_in"))
    )
    (net (code "153") (name "AVDD_3.0") (class "Default")
      (node (ref "U1") (pin "E10") (pinfunction "AVDD_3P0_E10") (pintype "power_in"))
      (node (ref "U1") (pin "E11") (pinfunction "AVDD_3P0_E11") (pintype "power_in"))
      (node (ref "U1") (pin "E12") (pinfunction "AVDD_3P0_E12") (pintype "power_in"))
      (node (ref "U1") (pin "E6") (pinfunction "AVDD_3P0_E6") (pintype "power_in"))
      (node (ref "U1") (pin "E7") (pinfunction "AVDD_3P0_E7") (pintype "power_in"))
    )
    (net (code "154") (name "AVDD_VCA_1.8") (class "Default")
      (node (ref "U1") (pin "F11") (pinfunction "AVDD_VCA_1P8_F11") (pintype "power_in"))
      (node (ref "U1") (pin "F12") (pinfunction "AVDD_VCA_1P8_F12") (pintype "power_in"))
      (node (ref "U1") (pin "F6") (pinfunction "AVDD_VCA_1P8_F6") (pintype "power_in"))
      (node (ref "U1") (pin "F7") (pinfunction "AVDD_VCA_1P8_F7") (pintype "power_in"))
      (node (ref "U1") (pin "G11") (pinfunction "AVDD_VCA_1P8_G11") (pintype "power_in"))
      (node (ref "U1") (pin "G12") (pinfunction "AVDD_VCA_1P8_G12") (pintype "power_in"))
      (node (ref "U1") (pin "G6") (pinfunction "AVDD_VCA_1P8_G6") (pintype "power_in"))
      (node (ref "U1") (pin "G7") (pinfunction "AVDD_VCA_1P8_G7") (pintype "power_in"))
      (node (ref "U1") (pin "H11") (pinfunction "AVDD_VCA_1P8_H11") (pintype "power_in"))
      (node (ref "U1") (pin "H12") (pinfunction "AVDD_VCA_1P8_H12") (pintype "power_in"))
      (node (ref "U1") (pin "H13") (pinfunction "AVDD_VCA_1P8_H13") (pintype "power_in"))
      (node (ref "U1") (pin "H6") (pinfunction "AVDD_VCA_1P8_H6") (pintype "power_in"))
      (node (ref "U1") (pin "H7") (pinfunction "AVDD_VCA_1P8_H7") (pintype "power_in"))
      (node (ref "U1") (pin "J11") (pinfunction "AVDD_VCA_1P8_J11") (pintype "power_in"))
      (node (ref "U1") (pin "J12") (pinfunction "AVDD_VCA_1P8_J12") (pintype "power_in"))
      (node (ref "U1") (pin "J6") (pinfunction "AVDD_VCA_1P8_J6") (pintype "power_in"))
      (node (ref "U1") (pin "J7") (pinfunction "AVDD_VCA_1P8_J7") (pintype "power_in"))
    )
    (net (code "155") (name "DVDD_1.2") (class "Default")
      (node (ref "U1") (pin "L3") (pinfunction "DVDD_1P2_L3") (pintype "power_in"))
      (node (ref "U1") (pin "M12") (pinfunction "DVDD_1P2_M12") (pintype "power_in"))
      (node (ref "U1") (pin "M13") (pinfunction "DVDD_1P2_M13") (pintype "power_in"))
      (node (ref "U1") (pin "M14") (pinfunction "DVDD_1P2_M14") (pintype "power_in"))
      (node (ref "U1") (pin "M4") (pinfunction "DVDD_1P2_M4") (pintype "power_in"))
      (node (ref "U1") (pin "M5") (pinfunction "DVDD_1P2_M5") (pintype "power_in"))
      (node (ref "U1") (pin "M6") (pinfunction "DVDD_1P2_M6") (pintype "power_in"))
      (node (ref "U1") (pin "N12") (pinfunction "DVDD_1P2_N12") (pintype "power_in"))
      (node (ref "U1") (pin "N13") (pinfunction "DVDD_1P2_N13") (pintype "power_in"))
      (node (ref "U1") (pin "N14") (pinfunction "DVDD_1P2_N14") (pintype "power_in"))
      (node (ref "U1") (pin "N15") (pinfunction "DVDD_1P2_N15") (pintype "power_in"))
      (node (ref "U1") (pin "N16") (pinfunction "DVDD_1P2_N16") (pintype "power_in"))
      (node (ref "U1") (pin "N2") (pinfunction "DVDD_1P2_N2") (pintype "power_in"))
      (node (ref "U1") (pin "N3") (pinfunction "DVDD_1P2_N3") (pintype "power_in"))
      (node (ref "U1") (pin "N4") (pinfunction "DVDD_1P2_N4") (pintype "power_in"))
      (node (ref "U1") (pin "N5") (pinfunction "DVDD_1P2_N5") (pintype "power_in"))
      (node (ref "U1") (pin "N6") (pinfunction "DVDD_1P2_N6") (pintype "power_in"))
      (node (ref "U1") (pin "P15") (pinfunction "DVDD_1P2_P15") (pintype "power_in"))
      (node (ref "U1") (pin "P16") (pinfunction "DVDD_1P2_P16") (pintype "power_in"))
      (node (ref "U1") (pin "P2") (pinfunction "DVDD_1P2_P2") (pintype "power_in"))
      (node (ref "U1") (pin "P3") (pinfunction "DVDD_1P2_P3") (pintype "power_in"))
    )
    (net (code "156") (name "DVDD_1.8") (class "Default")
      (node (ref "R104") (pin "2") (pinfunction "2_2") (pintype "passive"))
      (node (ref "R179") (pin "2") (pinfunction "2_2") (pintype "passive"))
      (node (ref "U1") (pin "P11") (pinfunction "DVDD_1P8_P11") (pintype "power_in"))
      (node (ref "U1") (pin "P12") (pinfunction "DVDD_1P8_P12") (pintype "power_in"))
      (node (ref "U1") (pin "P13") (pinfunction "DVDD_1P8_P13") (pintype "power_in"))
      (node (ref "U1") (pin "P14") (pinfunction "DVDD_1P8_P14") (pintype "power_in"))
      (node (ref "U1") (pin "P4") (pinfunction "DVDD_1P8_P4") (pintype "power_in"))
      (node (ref "U1") (pin "P5") (pinfunction "DVDD_1P8_P5") (pintype "power_in"))
      (node (ref "U1") (pin "P6") (pinfunction "DVDD_1P8_P6") (pintype "power_in"))
      (node (ref "U1") (pin "P7") (pinfunction "DVDD_1P8_P7") (pintype "power_in"))
    )
    (net (code "157") (name "GND") (class "Default")
      (node (ref "R184") (pin "1") (pinfunction "1_1") (pintype "passive"))
      (node (ref "R185") (pin "1") (pinfunction "1_1") (pintype "passive"))
      (node (ref "R186") (pin "1") (pinfunction "1_1") (pintype "passive"))
      (node (ref "U1") (pin "E1") (pinfunction "AVSS_E1") (pintype "power_in"))
      (node (ref "U1") (pin "E15") (pinfunction "AVSS_E15") (pintype "power_in"))
      (node (ref "U1") (pin "E16") (pinfunction "AVSS_E16") (pintype "power_in"))
      (node (ref "U1") (pin "E17") (pinfunction "AVSS_E17") (pintype "power_in"))
      (node (ref "U1") (pin "E2") (pinfunction "AVSS_E2") (pintype "power_in"))
      (node (ref "U1") (pin "E3") (pinfunction "AVSS_E3") (pintype "power_in"))
      (node (ref "U1") (pin "F10") (pinfunction "AVSS_F10") (pintype "power_in"))
      (node (ref "U1") (pin "F15") (pinfunction "AVSS_F15") (pintype "power_in"))
      (node (ref "U1") (pin "F3") (pinfunction "AVSS_F3") (pintype "power_in"))
      (node (ref "U1") (pin "F8") (pinfunction "AVSS_F8") (pintype "power_in"))
      (node (ref "U1") (pin "F9") (pinfunction "AVSS_F9") (pintype "power_in"))
      (node (ref "U1") (pin "G10") (pinfunction "AVSS_G10") (pintype "power_in"))
      (node (ref "U1") (pin "G15") (pinfunction "AVSS_G15") (pintype "power_in"))
      (node (ref "U1") (pin "G16") (pinfunction "AVSS_G16") (pintype "power_in"))
      (node (ref "U1") (pin "G17") (pinfunction "AVSS_G17") (pintype "power_in"))
      (node (ref "U1") (pin "G3") (pinfunction "AVSS_G3") (pintype "power_in"))
      (node (ref "U1") (pin "G8") (pinfunction "AVSS_G8") (pintype "power_in"))
      (node (ref "U1") (pin "G9") (pinfunction "AVSS_G9") (pintype "power_in"))
      (node (ref "U1") (pin "H1") (pinfunction "AVSS_H1") (pintype "power_in"))
      (node (ref "U1") (pin "H10") (pinfunction "AVSS_H10") (pintype "power_in"))
      (node (ref "U1") (pin "H2") (pinfunction "AVSS_H2") (pintype "power_in"))
      (node (ref "U1") (pin "H3") (pinfunction "AVSS_H3") (pintype "power_in"))
      (node (ref "U1") (pin "H8") (pinfunction "AVSS_H8") (pintype "power_in"))
      (node (ref "U1") (pin "H9") (pinfunction "AVSS_H9") (pintype "power_in"))
      (node (ref "U1") (pin "J10") (pinfunction "AVSS_J10") (pintype "power_in"))
      (node (ref "U1") (pin "J3") (pinfunction "AVSS_J3") (pintype "power_in"))
      (node (ref "U1") (pin "J8") (pinfunction "AVSS_J8") (pintype "power_in"))
      (node (ref "U1") (pin "J9") (pinfunction "AVSS_J9") (pintype "power_in"))
      (node (ref "U1") (pin "K1") (pinfunction "AVSS_K1") (pintype "power_in"))
      (node (ref "U1") (pin "K10") (pinfunction "AVSS_K10") (pintype "power_in"))
      (node (ref "U1") (pin "K2") (pinfunction "AVSS_K2") (pintype "power_in"))
      (node (ref "U1") (pin "K3") (pinfunction "AVSS_K3") (pintype "power_in"))
      (node (ref "U1") (pin "K8") (pinfunction "AVSS_K8") (pintype "power_in"))
      (node (ref "U1") (pin "K9") (pinfunction "AVSS_K9") (pintype "power_in"))
      (node (ref "U1") (pin "L10") (pinfunction "AVSS_L10") (pintype "power_in"))
      (node (ref "U1") (pin "L8") (pinfunction "AVSS_L8") (pintype "power_in"))
      (node (ref "U1") (pin "L9") (pinfunction "AVSS_L9") (pintype "power_in"))
      (node (ref "U1") (pin "M10") (pinfunction "DVSS_M10") (pintype "power_in"))
      (node (ref "U1") (pin "M11") (pinfunction "DVSS_M11") (pintype "power_in"))
      (node (ref "U1") (pin "M3") (pinfunction "DVSS_M3") (pintype "power_in"))
      (node (ref "U1") (pin "M7") (pinfunction "DVSS_M7") (pintype "power_in"))
      (node (ref "U1") (pin "M8") (pinfunction "DVSS_M8") (pintype "power_in"))
      (node (ref "U1") (pin "M9") (pinfunction "DVSS_M9") (pintype "power_in"))
      (node (ref "U1") (pin "N10") (pinfunction "DVSS_N10") (pintype "power_in"))
      (node (ref "U1") (pin "N11") (pinfunction "DVSS_N11") (pintype "power_in"))
      (node (ref "U1") (pin "N7") (pinfunction "DVSS_N7") (pintype "power_in"))
      (node (ref "U1") (pin "N8") (pinfunction "DVSS_N8") (pintype "power_in"))
      (node (ref "U1") (pin "N9") (pinfunction "DVSS_N9") (pintype "power_in"))
      (node (ref "U1") (pin "P10") (pinfunction "DVSS_P10") (pintype "power_in"))
      (node (ref "U1") (pin "P8") (pinfunction "DVSS_P8") (pintype "power_in"))
      (node (ref "U1") (pin "P9") (pinfunction "DVSS_P9") (pintype "power_in"))
    )
    (net (code "158") (name "Net-(U1D-SEN)") (class "Default")
      (node (ref "R103") (pin "2") (pinfunction "2_2") (pintype "passive"))
      (node (ref "U1") (pin "K17") (pinfunction "SEN_K17") (pintype "input"))
    )
    (net (code "159") (name "Net-(U1E-ADC_CLKM)") (class "Default")
      (node (ref "C172") (pin "1") (pinfunction "1_1") (pintype "passive"))
      (node (ref "R107") (pin "2") (pinfunction "2_2") (pintype "passive"))
      (node (ref "U1") (pin "J2") (pinfunction "ADC_CLKM_J2") (pintype "input"))
    )
    (net (code "160") (name "Net-(U1E-ADC_CLKP)") (class "Default")
      (node (ref "C171") (pin "1") (pinfunction "1_1") (pintype "passive"))
      (node (ref "R107") (pin "1") (pinfunction "1_1") (pintype "passive"))
      (node (ref "U1") (pin "J1") (pinfunction "ADC_CLKP_J1") (pintype "input"))
    )
    (net (code "161") (name "Net-(U1E-CLKM_1X)") (class "Default")
      (node (ref "C170") (pin "1") (pinfunction "1_1") (pintype "passive"))
      (node (ref "R106") (pin "2") (pinfunction "2_2") (pintype "passive"))
      (node (ref "U1") (pin "H16") (pinfunction "CLKM_1X_H16") (pintype "input"))
    )
    (net (code "162") (name "Net-(U1E-CLKM_16X)") (class "Default")
      (node (ref "C168") (pin "1") (pinfunction "1_1") (pintype "passive"))
      (node (ref "R105") (pin "2") (pinfunction "2_2") (pintype "passive"))
      (node (ref "U1") (pin "F17") (pinfunction "CLKM_16X_F17") (pintype "input"))
    )
    (net (code "163") (name "Net-(U1E-CLKP_1X)") (class "Default")
      (node (ref "C169") (pin "1") (pinfunction "1_1") (pintype "passive"))
      (node (ref "R106") (pin "1") (pinfunction "1_1") (pintype "passive"))
      (node (ref "U1") (pin "H17") (pinfunction "CLKP_1X_H17") (pintype "input"))
    )
    (net (code "164") (name "Net-(U1E-CLKP_16X)") (class "Default")
      (node (ref "C167") (pin "1") (pinfunction "1_1") (pintype "passive"))
      (node (ref "R105") (pin "1") (pinfunction "1_1") (pintype "passive"))
      (node (ref "U1") (pin "F16") (pinfunction "CLKP_16X_F16") (pintype "input"))
    )
    (net (code "165") (name "Net-(U1G-SYNCM_SERDES)") (class "Default")
      (node (ref "C248") (pin "1") (pinfunction "1_1") (pintype "passive"))
      (node (ref "R182") (pin "2") (pinfunction "2_2") (pintype "passive"))
      (node (ref "R185") (pin "2") (pinfunction "2_2") (pintype "passive"))
      (node (ref "U1") (pin "L2") (pinfunction "SYNCM_SERDES_L2") (pintype "passive"))
    )
    (net (code "166") (name "Net-(U1G-SYNCP_SERDES)") (class "Default")
      (node (ref "C227") (pin "1") (pinfunction "1_1") (pintype "passive"))
      (node (ref "R104") (pin "1") (pinfunction "1_1") (pintype "passive"))
      (node (ref "R180") (pin "2") (pinfunction "2_2") (pintype "passive"))
      (node (ref "R184") (pin "2") (pinfunction "2_2") (pintype "passive"))
      (node (ref "U1") (pin "L1") (pinfunction "SYNCP_SERDES_L1") (pintype "passive"))
    )
    (net (code "167") (name "Net-(U1G-SYSREFM_SERDES)") (class "Default")
      (node (ref "C164") (pin "1") (pinfunction "1_1") (pintype "passive"))
      (node (ref "C166") (pin "1") (pinfunction "1_1") (pintype "passive"))
      (node (ref "R179") (pin "1") (pinfunction "1_1") (pintype "passive"))
      (node (ref "U1") (pin "M2") (pinfunction "SYSREFM_SERDES_M2") (pintype "passive"))
    )
    (net (code "168") (name "Net-(U1G-SYSREFP_SERDES)") (class "Default")
      (node (ref "C163") (pin "1") (pinfunction "1_1") (pintype "passive"))
      (node (ref "C165") (pin "1") (pinfunction "1_1") (pintype "passive"))
      (node (ref "R186") (pin "2") (pinfunction "2_2") (pintype "passive"))
      (node (ref "U1") (pin "M1") (pinfunction "SYSREFP_SERDES_M1") (pintype "passive"))
    )
    (net (code "169") (name "Net-(U1H-BIAS_0P75)") (class "Default")
      (node (ref "C176") (pin "1") (pinfunction "1_1") (pintype "passive"))
      (node (ref "TP50") (pin "1") (pintype "passive"))
      (node (ref "U1") (pin "A9") (pinfunction "BIAS_0P75_A9") (pintype "passive"))
    )
    (net (code "170") (name "Net-(U1H-BIAS_1P2)") (class "Default")
      (node (ref "C177") (pin "1") (pinfunction "1_1") (pintype "passive"))
      (node (ref "TP51") (pin "1") (pintype "passive"))
      (node (ref "U1") (pin "G4") (pinfunction "BIAS_1P2_G4") (pintype "passive"))
    )
    (net (code "171") (name "Net-(U1H-BIAS_2P8)") (class "Default")
      (node (ref "C178") (pin "1") (pinfunction "1_1") (pintype "passive"))
      (node (ref "TP52") (pin "1") (pintype "passive"))
      (node (ref "U1") (pin "G5") (pinfunction "BIAS_2P8_G5") (pintype "passive"))
    )
    (net (code "172") (name "unconnected-(U1D-NC-PadK15)") (class "Default")
      (node (ref "U1") (pin "K15") (pinfunction "NC_K15") (pintype "passive+no_connect"))
    )
    (net (code "173") (name "unconnected-(U1H-NC-PadD9)") (class "Default")
      (node (ref "U1") (pin "D9") (pinfunction "NC_D9") (pintype "passive+no_connect"))
    )
    (net (code "174") (name "unconnected-(U1H-NC-PadE4)") (class "Default")
      (node (ref "U1") (pin "E4") (pinfunction "NC_E4") (pintype "passive+no_connect"))
    )
    (net (code "175") (name "unconnected-(U1H-NC-PadE5)") (class "Default")
      (node (ref "U1") (pin "E5") (pinfunction "NC_E5") (pintype "passive+no_connect"))
    )
    (net (code "176") (name "unconnected-(U1H-NC-PadE13)") (class "Default")
      (node (ref "U1") (pin "E13") (pinfunction "NC_E13") (pintype "passive+no_connect"))
    )
    (net (code "177") (name "unconnected-(U1H-NC-PadE14)") (class "Default")
      (node (ref "U1") (pin "E14") (pinfunction "NC_E14") (pintype "passive+no_connect"))
    )
    (net (code "178") (name "unconnected-(U1H-NC-PadH14)") (class "Default")
      (node (ref "U1") (pin "H14") (pinfunction "NC_H14") (pintype "passive+no_connect"))
    )
    (net (code "179") (name "unconnected-(U1H-NC-PadH15)") (class "Default")
      (node (ref "U1") (pin "H15") (pinfunction "NC_H15") (pintype "passive+no_connect"))
    )
    (net (code "180") (name "unconnected-(U1H-NC-PadJ15)") (class "Default")
      (node (ref "U1") (pin "J15") (pinfunction "NC_J15") (pintype "passive+no_connect"))
    )
    (net (code "181") (name "unconnected-(U1J-NC-PadB9)") (class "Default")
      (node (ref "U1") (pin "B9") (pinfunction "NC_B9") (pintype "passive+no_connect"))
    )
    (net (code "182") (name "unconnected-(U1J-NC-PadC9)") (class "Default")
      (node (ref "U1") (pin "C9") (pinfunction "NC_C9") (pintype "passive+no_connect"))
    )
    (net (code "183") (name "unconnected-(U1J-NC-PadE8)") (class "Default")
      (node (ref "U1") (pin "E8") (pinfunction "NC_E8") (pintype "passive+no_connect"))
    )
    (net (code "184") (name "unconnected-(U1J-NC-PadE9)") (class "Default")
      (node (ref "U1") (pin "E9") (pinfunction "NC_E9") (pintype "passive+no_connect"))
    )
    (net (code "185") (name "unconnected-(U1J-NC-PadF4)") (class "Default")
      (node (ref "U1") (pin "F4") (pinfunction "NC_F4") (pintype "passive+no_connect"))
    )
    (net (code "186") (name "unconnected-(U1J-NC-PadF5)") (class "Default")
      (node (ref "U1") (pin "F5") (pinfunction "NC_F5") (pintype "passive+no_connect"))
    )
    (net (code "187") (name "unconnected-(U1J-NC-PadF13)") (class "Default")
      (node (ref "U1") (pin "F13") (pinfunction "NC_F13") (pintype "passive+no_connect"))
    )
    (net (code "188") (name "unconnected-(U1J-NC-PadF14)") (class "Default")
      (node (ref "U1") (pin "F14") (pinfunction "NC_F14") (pintype "passive+no_connect"))
    )
    (net (code "189") (name "unconnected-(U1J-NC-PadG13)") (class "Default")
      (node (ref "U1") (pin "G13") (pinfunction "NC_G13") (pintype "passive+no_connect"))
    )
    (net (code "190") (name "unconnected-(U1J-NC-PadG14)") (class "Default")
      (node (ref "U1") (pin "G14") (pinfunction "NC_G14") (pintype "passive+no_connect"))
    )
    (net (code "191") (name "unconnected-(U1J-NC-PadJ13)") (class "Default")
      (node (ref "U1") (pin "J13") (pinfunction "NC_J13") (pintype "passive+no_connect"))
    )
    (net (code "192") (name "unconnected-(U1J-NC-PadK13)") (class "Default")
      (node (ref "U1") (pin "K13") (pinfunction "NC_K13") (pintype "passive+no_connect"))
    )
    (net (code "193") (name "unconnected-(U1J-NC-PadK14)") (class "Default")
      (node (ref "U1") (pin "K14") (pinfunction "NC_K14") (pintype "passive+no_connect"))
    )
    (net (code "194") (name "unconnected-(U1J-NC-PadL4)") (class "Default")
      (node (ref "U1") (pin "L4") (pinfunction "NC_L4") (pintype "passive+no_connect"))
    )
    (net (code "195") (name "unconnected-(U1J-NC-PadL5)") (class "Default")
      (node (ref "U1") (pin "L5") (pinfunction "NC_L5") (pintype "passive+no_connect"))
    )
    (net (code "196") (name "unconnected-(U1J-NC-PadL13)") (class "Default")
      (node (ref "U1") (pin "L13") (pinfunction "NC_L13") (pintype "passive+no_connect"))
    )
    (net (code "197") (name "unconnected-(U1J-NC-PadL14)") (class "Default")
      (node (ref "U1") (pin "L14") (pinfunction "NC_L14") (pintype "passive+no_connect"))
    )
    (net (code "198") (name "unconnected-(U1J-NC-PadL15)") (class "Default")
      (node (ref "U1") (pin "L15") (pinfunction "NC_L15") (pintype "passive+no_connect"))
    )
    (net (code "199") (name "unconnected-(U1J-NC-PadR5)") (class "Default")
      (node (ref "U1") (pin "R5") (pinfunction "NC_R5") (pintype "passive+no_connect"))
    )
    (net (code "200") (name "unconnected-(U1J-NC-PadR9)") (class "Default")
      (node (ref "U1") (pin "R9") (pinfunction "NC_R9") (pintype "passive+no_connect"))
    )
    (net (code "201") (name "unconnected-(U1J-NC-PadR13)") (class "Default")
      (node (ref "U1") (pin "R13") (pinfunction "NC_R13") (pintype "passive+no_connect"))
    )
  )
)
